# Sheet1.net
KiCad netlist of a schematic drawn in Altium Designer
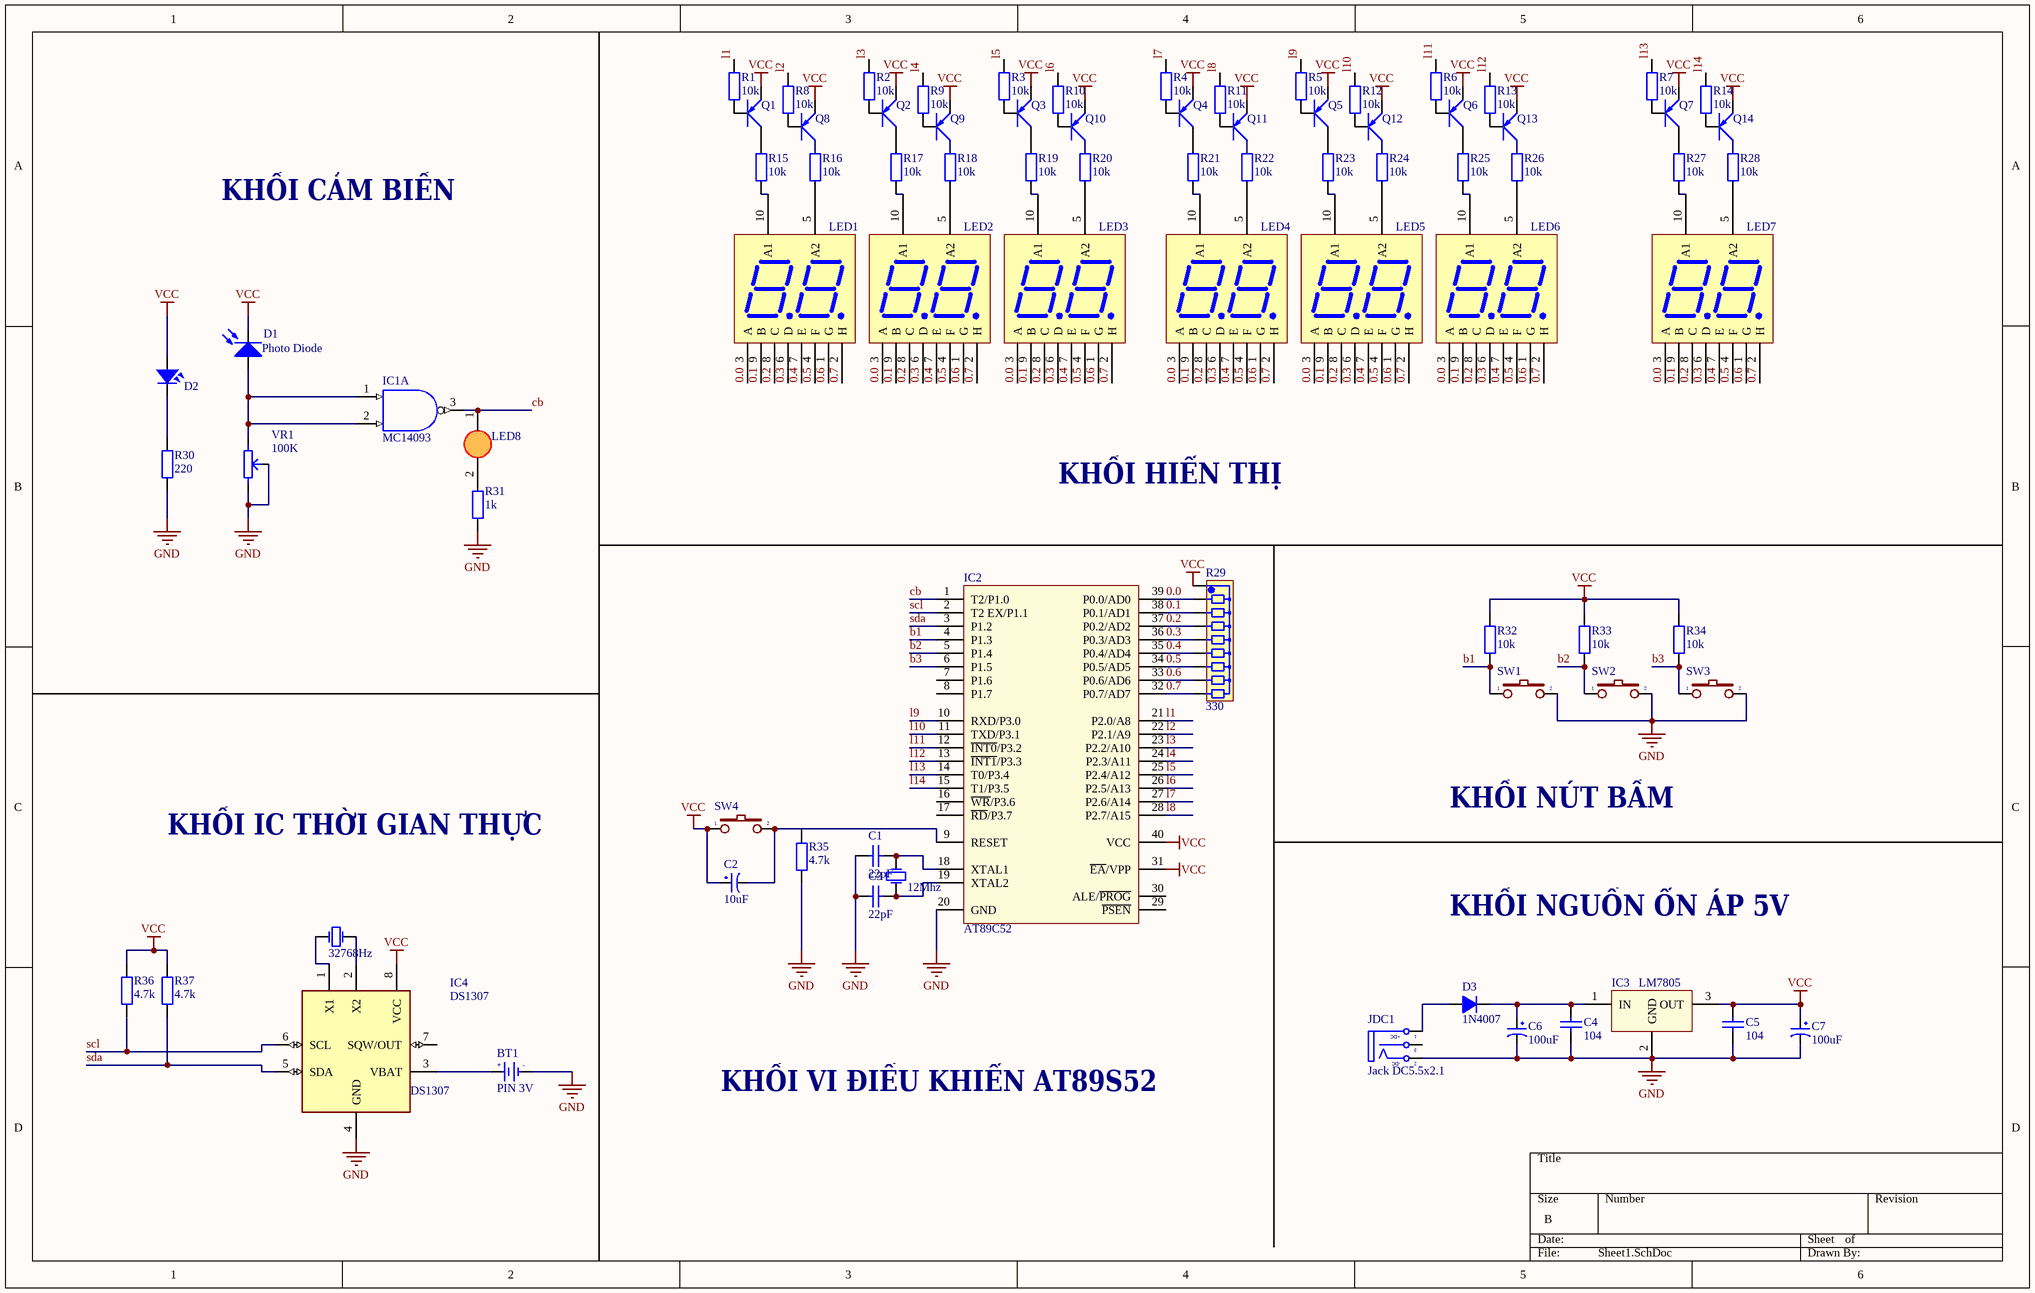
[diagram p0: Sheet1.SchDoc]

(export (version "E")
  (design (tool "Eeschema 10.0.6"))
  (components
    (comp (ref "BT1")
      (value "PIN 3V")
      (footprint "PIN3V")
      (description "Battery 3VDC")
      (libsource (lib "THU VIEN SCH") (part "PIN 3V"))
    )
    (comp (ref "C1")
      (value "22pF")
      (footprint "tu gom")
      (description "Cắm")
      (libsource (lib "THU VIEN SCH") (part "Tu gom 22pF 50V"))
    )
    (comp (ref "C2")
      (value "10uF")
      (footprint "tu hoa 4mm")
      (description "Cắm")
      (libsource (lib "THU VIEN SCH") (part "Tu Hoa 10uF 16V 4x7"))
    )
    (comp (ref "C3")
      (value "22pF")
      (footprint "tu gom")
      (description "Cắm")
      (libsource (lib "THU VIEN SCH") (part "Tu gom 22pF 50V"))
    )
    (comp (ref "C4")
      (value "104")
      (footprint "tu gom")
      (description "Cắm")
      (libsource (lib "THU VIEN SCH") (part "Tu gom 104 50V"))
    )
    (comp (ref "C5")
      (value "104")
      (footprint "tu gom")
      (description "Cắm")
      (libsource (lib "THU VIEN SCH") (part "Tu gom 104 50V"))
    )
    (comp (ref "C6")
      (value "100uF")
      (footprint "tu hoa 5mm")
      (description "Cắm")
      (libsource (lib "THU VIEN SCH") (part "Tu Hoa 100uF 16V 5x7"))
    )
    (comp (ref "C7")
      (value "100uF")
      (footprint "tu hoa 5mm")
      (description "Cắm")
      (libsource (lib "THU VIEN SCH") (part "Tu Hoa 100uF 16V 5x7"))
    )
    (comp (ref "D1")
      (value "Photo Diode")
      (footprint "LED-5-Green")
      (description "Photosensitive Diode")
      (libsource (lib "syhaunguyen") (part "Photo Diode"))
    )
    (comp (ref "D2")
      (value "Phat")
      (footprint "LED-3")
      (description "LED phat hong ngoai")
      (libsource (lib "syhaunguyen") (part "LED"))
    )
    (comp (ref "D3")
      (value "1N4007")
      (footprint "Diode 1N4007")
      (description "Diode 1A")
      (libsource (lib "syhaunguyen") (part "D1A"))
    )
    (comp (ref "IC1")
      (value "MC14093")
      (footprint "DIP14/W0.3")
      (description "Quad 2-Input NAND Schmitt Trigger")
      (libsource (lib "syhaunguyen") (part "MC14093"))
    )
    (comp (ref "IC2")
      (value "AT89C52")
      (footprint "DIP40/W0.6")
      (description "Cắm")
      (libsource (lib "THU VIEN SCH") (part "AT89C52"))
    )
    (comp (ref "IC3")
      (value "LM7805")
      (footprint "QTO-220")
      (description "On ap +, from + 5 to + 24VDC")
      (libsource (lib "THU VIEN SCH") (part "LM78xx"))
    )
    (comp (ref "IC4")
      (value "DS1307")
      (footprint "DIL08")
      (description "Real Time Clock (RTC) IC Clock/Calendar 56B IÂ²C, 2-Wire Serial 8-SOIC (0.154, 3.90mm Width)")
      (fields (field (name "MF") "Analog Devices"))
      (libsource (lib "DS1307") (part "DS1307"))
    )
    (comp (ref "JDC1")
      (value "Jack DC5.5x2.1")
      (footprint "DC-IN")
      (description "Cắm")
      (libsource (lib "THU VIEN SCH") (part "Jac_DC"))
    )
    (comp (ref "LED1")
      (value "Led 7 0.36 3 Số Anot ( Sáng Đỏ)")
      (footprint "LED 7 THANH_0.36x2")
      (description "Cắm")
      (libsource (lib "THU VIEN SCH") (part "LED 7 2 SO 0.36_A"))
    )
    (comp (ref "LED2")
      (value "Led 7 0.36 3 Số Anot ( Sáng Đỏ)")
      (footprint "LED 7 THANH_0.36x2")
      (description "Cắm")
      (libsource (lib "THU VIEN SCH") (part "LED 7 2 SO 0.36_A"))
    )
    (comp (ref "LED3")
      (value "Led 7 0.36 3 Số Anot ( Sáng Đỏ)")
      (footprint "LED 7 THANH_0.36x2")
      (description "Cắm")
      (libsource (lib "THU VIEN SCH") (part "LED 7 2 SO 0.36_A"))
    )
    (comp (ref "LED4")
      (value "Led 7 0.36 3 Số Anot ( Sáng Đỏ)")
      (footprint "LED 7 THANH_0.36x2")
      (description "Cắm")
      (libsource (lib "THU VIEN SCH") (part "LED 7 2 SO 0.36_A"))
    )
    (comp (ref "LED5")
      (value "Led 7 0.36 3 Số Anot ( Sáng Đỏ)")
      (footprint "LED 7 THANH_0.36x2")
      (description "Cắm")
      (libsource (lib "THU VIEN SCH") (part "LED 7 2 SO 0.36_A"))
    )
    (comp (ref "LED6")
      (value "Led 7 0.36 3 Số Anot ( Sáng Đỏ)")
      (footprint "LED 7 THANH_0.36x2")
      (description "Cắm")
      (libsource (lib "THU VIEN SCH") (part "LED 7 2 SO 0.36_A"))
    )
    (comp (ref "LED7")
      (value "Led 7 0.36 3 Số Anot ( Sáng Đỏ)")
      (footprint "LED 7 THANH_0.36x2")
      (description "Cắm")
      (libsource (lib "THU VIEN SCH") (part "LED 7 2 SO 0.36_A"))
    )
    (comp (ref "LED8")
      (value "~")
      (footprint "LED 3mm Do")
      (description "Cắm")
      (libsource (lib "THU VIEN SCH") (part "LED 3mm Do"))
    )
    (comp (ref "Q1")
      (value "~")
      (footprint "QTO-92")
      (description "PNP 600mW, ECB")
      (libsource (lib "syhaunguyen") (part "A1015"))
    )
    (comp (ref "Q2")
      (value "~")
      (footprint "QTO-92")
      (description "PNP 600mW, ECB")
      (libsource (lib "syhaunguyen") (part "A1015"))
    )
    (comp (ref "Q3")
      (value "~")
      (footprint "QTO-92")
      (description "PNP 600mW, ECB")
      (libsource (lib "syhaunguyen") (part "A1015"))
    )
    (comp (ref "Q4")
      (value "~")
      (footprint "QTO-92")
      (description "PNP 600mW, ECB")
      (libsource (lib "syhaunguyen") (part "A1015"))
    )
    (comp (ref "Q5")
      (value "~")
      (footprint "QTO-92")
      (description "PNP 600mW, ECB")
      (libsource (lib "syhaunguyen") (part "A1015"))
    )
    (comp (ref "Q6")
      (value "~")
      (footprint "QTO-92")
      (description "PNP 600mW, ECB")
      (libsource (lib "syhaunguyen") (part "A1015"))
    )
    (comp (ref "Q7")
      (value "~")
      (footprint "QTO-92")
      (description "PNP 600mW, ECB")
      (libsource (lib "syhaunguyen") (part "A1015"))
    )
    (comp (ref "Q8")
      (value "~")
      (footprint "QTO-92")
      (description "PNP 600mW, ECB")
      (libsource (lib "syhaunguyen") (part "A1015"))
    )
    (comp (ref "Q9")
      (value "~")
      (footprint "QTO-92")
      (description "PNP 600mW, ECB")
      (libsource (lib "syhaunguyen") (part "A1015"))
    )
    (comp (ref "Q10")
      (value "~")
      (footprint "QTO-92")
      (description "PNP 600mW, ECB")
      (libsource (lib "syhaunguyen") (part "A1015"))
    )
    (comp (ref "Q11")
      (value "~")
      (footprint "QTO-92")
      (description "PNP 600mW, ECB")
      (libsource (lib "syhaunguyen") (part "A1015"))
    )
    (comp (ref "Q12")
      (value "~")
      (footprint "QTO-92")
      (description "PNP 600mW, ECB")
      (libsource (lib "syhaunguyen") (part "A1015"))
    )
    (comp (ref "Q13")
      (value "~")
      (footprint "QTO-92")
      (description "PNP 600mW, ECB")
      (libsource (lib "syhaunguyen") (part "A1015"))
    )
    (comp (ref "Q14")
      (value "~")
      (footprint "QTO-92")
      (description "PNP 600mW, ECB")
      (libsource (lib "syhaunguyen") (part "A1015"))
    )
    (comp (ref "R1")
      (value "10k")
      (footprint "tro vach 1/4w")
      (description "Cắm")
      (libsource (lib "THU VIEN SCH") (part "Tro Vach 1/4W 1% 10k"))
    )
    (comp (ref "R2")
      (value "10k")
      (footprint "tro vach 1/4w")
      (description "Cắm")
      (libsource (lib "THU VIEN SCH") (part "Tro Vach 1/4W 1% 10k"))
    )
    (comp (ref "R3")
      (value "10k")
      (footprint "tro vach 1/4w")
      (description "Cắm")
      (libsource (lib "THU VIEN SCH") (part "Tro Vach 1/4W 1% 10k"))
    )
    (comp (ref "R4")
      (value "10k")
      (footprint "tro vach 1/4w")
      (description "Cắm")
      (libsource (lib "THU VIEN SCH") (part "Tro Vach 1/4W 1% 10k"))
    )
    (comp (ref "R5")
      (value "10k")
      (footprint "tro vach 1/4w")
      (description "Cắm")
      (libsource (lib "THU VIEN SCH") (part "Tro Vach 1/4W 1% 10k"))
    )
    (comp (ref "R6")
      (value "10k")
      (footprint "tro vach 1/4w")
      (description "Cắm")
      (libsource (lib "THU VIEN SCH") (part "Tro Vach 1/4W 1% 10k"))
    )
    (comp (ref "R7")
      (value "10k")
      (footprint "tro vach 1/4w")
      (description "Cắm")
      (libsource (lib "THU VIEN SCH") (part "Tro Vach 1/4W 1% 10k"))
    )
    (comp (ref "R8")
      (value "10k")
      (footprint "tro vach 1/4w")
      (description "Cắm")
      (libsource (lib "THU VIEN SCH") (part "Tro Vach 1/4W 1% 10k"))
    )
    (comp (ref "R9")
      (value "10k")
      (footprint "tro vach 1/4w")
      (description "Cắm")
      (libsource (lib "THU VIEN SCH") (part "Tro Vach 1/4W 1% 10k"))
    )
    (comp (ref "R10")
      (value "10k")
      (footprint "tro vach 1/4w")
      (description "Cắm")
      (libsource (lib "THU VIEN SCH") (part "Tro Vach 1/4W 1% 10k"))
    )
    (comp (ref "R11")
      (value "10k")
      (footprint "tro vach 1/4w")
      (description "Cắm")
      (libsource (lib "THU VIEN SCH") (part "Tro Vach 1/4W 1% 10k"))
    )
    (comp (ref "R12")
      (value "10k")
      (footprint "tro vach 1/4w")
      (description "Cắm")
      (libsource (lib "THU VIEN SCH") (part "Tro Vach 1/4W 1% 10k"))
    )
    (comp (ref "R13")
      (value "10k")
      (footprint "tro vach 1/4w")
      (description "Cắm")
      (libsource (lib "THU VIEN SCH") (part "Tro Vach 1/4W 1% 10k"))
    )
    (comp (ref "R14")
      (value "10k")
      (footprint "tro vach 1/4w")
      (description "Cắm")
      (libsource (lib "THU VIEN SCH") (part "Tro Vach 1/4W 1% 10k"))
    )
    (comp (ref "R15")
      (value "10k")
      (footprint "tro vach 1/4w")
      (description "Cắm")
      (libsource (lib "THU VIEN SCH") (part "Tro Vach 1/4W 1% 10k"))
    )
    (comp (ref "R16")
      (value "10k")
      (footprint "tro vach 1/4w")
      (description "Cắm")
      (libsource (lib "THU VIEN SCH") (part "Tro Vach 1/4W 1% 10k"))
    )
    (comp (ref "R17")
      (value "10k")
      (footprint "tro vach 1/4w")
      (description "Cắm")
      (libsource (lib "THU VIEN SCH") (part "Tro Vach 1/4W 1% 10k"))
    )
    (comp (ref "R18")
      (value "10k")
      (footprint "tro vach 1/4w")
      (description "Cắm")
      (libsource (lib "THU VIEN SCH") (part "Tro Vach 1/4W 1% 10k"))
    )
    (comp (ref "R19")
      (value "10k")
      (footprint "tro vach 1/4w")
      (description "Cắm")
      (libsource (lib "THU VIEN SCH") (part "Tro Vach 1/4W 1% 10k"))
    )
    (comp (ref "R20")
      (value "10k")
      (footprint "tro vach 1/4w")
      (description "Cắm")
      (libsource (lib "THU VIEN SCH") (part "Tro Vach 1/4W 1% 10k"))
    )
    (comp (ref "R21")
      (value "10k")
      (footprint "tro vach 1/4w")
      (description "Cắm")
      (libsource (lib "THU VIEN SCH") (part "Tro Vach 1/4W 1% 10k"))
    )
    (comp (ref "R22")
      (value "10k")
      (footprint "tro vach 1/4w")
      (description "Cắm")
      (libsource (lib "THU VIEN SCH") (part "Tro Vach 1/4W 1% 10k"))
    )
    (comp (ref "R23")
      (value "10k")
      (footprint "tro vach 1/4w")
      (description "Cắm")
      (libsource (lib "THU VIEN SCH") (part "Tro Vach 1/4W 1% 10k"))
    )
    (comp (ref "R24")
      (value "10k")
      (footprint "tro vach 1/4w")
      (description "Cắm")
      (libsource (lib "THU VIEN SCH") (part "Tro Vach 1/4W 1% 10k"))
    )
    (comp (ref "R25")
      (value "10k")
      (footprint "tro vach 1/4w")
      (description "Cắm")
      (libsource (lib "THU VIEN SCH") (part "Tro Vach 1/4W 1% 10k"))
    )
    (comp (ref "R26")
      (value "10k")
      (footprint "tro vach 1/4w")
      (description "Cắm")
      (libsource (lib "THU VIEN SCH") (part "Tro Vach 1/4W 1% 10k"))
    )
    (comp (ref "R27")
      (value "10k")
      (footprint "tro vach 1/4w")
      (description "Cắm")
      (libsource (lib "THU VIEN SCH") (part "Tro Vach 1/4W 1% 10k"))
    )
    (comp (ref "R28")
      (value "10k")
      (footprint "tro vach 1/4w")
      (description "Cắm")
      (libsource (lib "THU VIEN SCH") (part "Tro Vach 1/4W 1% 10k"))
    )
    (comp (ref "R29")
      (value "330")
      (footprint "tro bang a9")
      (description "Cắm")
      (libsource (lib "THU VIEN SCH") (part "Tro Bang A9 330R"))
    )
    (comp (ref "R30")
      (value "220")
      (footprint "tro vach 1/4w")
      (description "Cắm")
      (libsource (lib "THU VIEN SCH") (part "Tro Vach 1/4W 1% 10k"))
    )
    (comp (ref "R31")
      (value "1k")
      (footprint "tro vach 1/4w")
      (description "Cắm")
      (libsource (lib "THU VIEN SCH") (part "Tro Vach 1/4W 5% 1k"))
    )
    (comp (ref "R32")
      (value "10k")
      (footprint "tro vach 1/4w")
      (description "Cắm")
      (libsource (lib "THU VIEN SCH") (part "Tro Vach 1/4W 1% 10k"))
    )
    (comp (ref "R33")
      (value "10k")
      (footprint "tro vach 1/4w")
      (description "Cắm")
      (libsource (lib "THU VIEN SCH") (part "Tro Vach 1/4W 1% 10k"))
    )
    (comp (ref "R34")
      (value "10k")
      (footprint "tro vach 1/4w")
      (description "Cắm")
      (libsource (lib "THU VIEN SCH") (part "Tro Vach 1/4W 1% 10k"))
    )
    (comp (ref "R35")
      (value "4.7k")
      (footprint "tro vach 1/4w")
      (description "Cắm")
      (libsource (lib "THU VIEN SCH") (part "Tro Vach 1/4W 1% 4.7k"))
    )
    (comp (ref "R36")
      (value "4.7k")
      (footprint "tro vach 1/4w")
      (description "Cắm")
      (libsource (lib "THU VIEN SCH") (part "Tro Vach 1/4W 1% 4.7k"))
    )
    (comp (ref "R37")
      (value "4.7k")
      (footprint "tro vach 1/4w")
      (description "Cắm")
      (libsource (lib "THU VIEN SCH") (part "Tro Vach 1/4W 1% 4.7k"))
    )
    (comp (ref "SW1")
      (value "~")
      (footprint "SW2")
      (description "Cắm")
      (libsource (lib "THU VIEN SCH") (part "Nut Nhan 2 Chan ( Dip )"))
    )
    (comp (ref "SW2")
      (value "~")
      (footprint "SW2")
      (description "Cắm")
      (libsource (lib "THU VIEN SCH") (part "Nut Nhan 2 Chan ( Dip )"))
    )
    (comp (ref "SW3")
      (value "~")
      (footprint "SW2")
      (description "Cắm")
      (libsource (lib "THU VIEN SCH") (part "Nut Nhan 2 Chan ( Dip )"))
    )
    (comp (ref "SW4")
      (value "~")
      (footprint "SW2")
      (description "Cắm")
      (libsource (lib "THU VIEN SCH") (part "Nut Nhan 2 Chan ( Dip )"))
    )
    (comp (ref "VR1")
      (value "100K")
      (footprint "BIEN TRO TAM GIAC")
      (description "Cắm")
      (libsource (lib "THU VIEN SCH") (part "Bien tro tam giac 1K"))
    )
    (comp (ref "Y1")
      (value "12Mhz")
      (footprint "THACH ANH CAM")
      (description "Cắm")
      (libsource (lib "THU VIEN SCH") (part "Thach Anh 8Mhz DIP"))
    )
    (comp (ref "Y2")
      (value "32768Hz")
      (footprint "XT2")
      (description "Cắm")
      (libsource (lib "THU VIEN SCH") (part "Thach Anh 8Mhz DIP"))
    )
  )
  (nets
    (net (code "1") (name "/0.0") (class "Default")
      (node (ref "IC2") (pin "39") (pinfunction "P0.0/AD0_39") (pintype "passive"))
      (node (ref "LED1") (pin "3") (pinfunction "A_3") (pintype "passive"))
      (node (ref "LED2") (pin "3") (pinfunction "A_3") (pintype "passive"))
      (node (ref "LED3") (pin "3") (pinfunction "A_3") (pintype "passive"))
      (node (ref "LED4") (pin "3") (pinfunction "A_3") (pintype "passive"))
      (node (ref "LED5") (pin "3") (pinfunction "A_3") (pintype "passive"))
      (node (ref "LED6") (pin "3") (pinfunction "A_3") (pintype "passive"))
      (node (ref "LED7") (pin "3") (pinfunction "A_3") (pintype "passive"))
      (node (ref "R29") (pin "2") (pinfunction "2_2") (pintype "passive"))
    )
    (net (code "2") (name "/0.1") (class "Default")
      (node (ref "IC2") (pin "38") (pinfunction "P0.1/AD1_38") (pintype "passive"))
      (node (ref "LED1") (pin "9") (pinfunction "B_9") (pintype "passive"))
      (node (ref "LED2") (pin "9") (pinfunction "B_9") (pintype "passive"))
      (node (ref "LED3") (pin "9") (pinfunction "B_9") (pintype "passive"))
      (node (ref "LED4") (pin "9") (pinfunction "B_9") (pintype "passive"))
      (node (ref "LED5") (pin "9") (pinfunction "B_9") (pintype "passive"))
      (node (ref "LED6") (pin "9") (pinfunction "B_9") (pintype "passive"))
      (node (ref "LED7") (pin "9") (pinfunction "B_9") (pintype "passive"))
      (node (ref "R29") (pin "3") (pinfunction "3_3") (pintype "passive"))
    )
    (net (code "3") (name "/0.2") (class "Default")
      (node (ref "IC2") (pin "37") (pinfunction "P0.2/AD2_37") (pintype "passive"))
      (node (ref "LED1") (pin "8") (pinfunction "C_8") (pintype "passive"))
      (node (ref "LED2") (pin "8") (pinfunction "C_8") (pintype "passive"))
      (node (ref "LED3") (pin "8") (pinfunction "C_8") (pintype "passive"))
      (node (ref "LED4") (pin "8") (pinfunction "C_8") (pintype "passive"))
      (node (ref "LED5") (pin "8") (pinfunction "C_8") (pintype "passive"))
      (node (ref "LED6") (pin "8") (pinfunction "C_8") (pintype "passive"))
      (node (ref "LED7") (pin "8") (pinfunction "C_8") (pintype "passive"))
      (node (ref "R29") (pin "4") (pinfunction "4_4") (pintype "passive"))
    )
    (net (code "4") (name "/0.3") (class "Default")
      (node (ref "IC2") (pin "36") (pinfunction "P0.3/AD3_36") (pintype "passive"))
      (node (ref "LED1") (pin "6") (pinfunction "D_6") (pintype "passive"))
      (node (ref "LED2") (pin "6") (pinfunction "D_6") (pintype "passive"))
      (node (ref "LED3") (pin "6") (pinfunction "D_6") (pintype "passive"))
      (node (ref "LED4") (pin "6") (pinfunction "D_6") (pintype "passive"))
      (node (ref "LED5") (pin "6") (pinfunction "D_6") (pintype "passive"))
      (node (ref "LED6") (pin "6") (pinfunction "D_6") (pintype "passive"))
      (node (ref "LED7") (pin "6") (pinfunction "D_6") (pintype "passive"))
      (node (ref "R29") (pin "5") (pinfunction "5_5") (pintype "passive"))
    )
    (net (code "5") (name "/0.4") (class "Default")
      (node (ref "IC2") (pin "35") (pinfunction "P0.4/AD4_35") (pintype "passive"))
      (node (ref "LED1") (pin "7") (pinfunction "E_7") (pintype "passive"))
      (node (ref "LED2") (pin "7") (pinfunction "E_7") (pintype "passive"))
      (node (ref "LED3") (pin "7") (pinfunction "E_7") (pintype "passive"))
      (node (ref "LED4") (pin "7") (pinfunction "E_7") (pintype "passive"))
      (node (ref "LED5") (pin "7") (pinfunction "E_7") (pintype "passive"))
      (node (ref "LED6") (pin "7") (pinfunction "E_7") (pintype "passive"))
      (node (ref "LED7") (pin "7") (pinfunction "E_7") (pintype "passive"))
      (node (ref "R29") (pin "6") (pinfunction "6_6") (pintype "passive"))
    )
    (net (code "6") (name "/0.5") (class "Default")
      (node (ref "IC2") (pin "34") (pinfunction "P0.5/AD5_34") (pintype "passive"))
      (node (ref "LED1") (pin "4") (pinfunction "F_4") (pintype "passive"))
      (node (ref "LED2") (pin "4") (pinfunction "F_4") (pintype "passive"))
      (node (ref "LED3") (pin "4") (pinfunction "F_4") (pintype "passive"))
      (node (ref "LED4") (pin "4") (pinfunction "F_4") (pintype "passive"))
      (node (ref "LED5") (pin "4") (pinfunction "F_4") (pintype "passive"))
      (node (ref "LED6") (pin "4") (pinfunction "F_4") (pintype "passive"))
      (node (ref "LED7") (pin "4") (pinfunction "F_4") (pintype "passive"))
      (node (ref "R29") (pin "7") (pinfunction "7_7") (pintype "passive"))
    )
    (net (code "7") (name "/0.6") (class "Default")
      (node (ref "IC2") (pin "33") (pinfunction "P0.6/AD6_33") (pintype "passive"))
      (node (ref "LED1") (pin "1") (pinfunction "G_1") (pintype "passive"))
      (node (ref "LED2") (pin "1") (pinfunction "G_1") (pintype "passive"))
      (node (ref "LED3") (pin "1") (pinfunction "G_1") (pintype "passive"))
      (node (ref "LED4") (pin "1") (pinfunction "G_1") (pintype "passive"))
      (node (ref "LED5") (pin "1") (pinfunction "G_1") (pintype "passive"))
      (node (ref "LED6") (pin "1") (pinfunction "G_1") (pintype "passive"))
      (node (ref "LED7") (pin "1") (pinfunction "G_1") (pintype "passive"))
      (node (ref "R29") (pin "8") (pinfunction "8_8") (pintype "passive"))
    )
    (net (code "8") (name "/0.7") (class "Default")
      (node (ref "IC2") (pin "32") (pinfunction "P0.7/AD7_32") (pintype "passive"))
      (node (ref "LED1") (pin "2") (pinfunction "H_2") (pintype "passive"))
      (node (ref "LED2") (pin "2") (pinfunction "H_2") (pintype "passive"))
      (node (ref "LED3") (pin "2") (pinfunction "H_2") (pintype "passive"))
      (node (ref "LED4") (pin "2") (pinfunction "H_2") (pintype "passive"))
      (node (ref "LED5") (pin "2") (pinfunction "H_2") (pintype "passive"))
      (node (ref "LED6") (pin "2") (pinfunction "H_2") (pintype "passive"))
      (node (ref "LED7") (pin "2") (pinfunction "H_2") (pintype "passive"))
      (node (ref "R29") (pin "9") (pinfunction "9_9") (pintype "passive"))
    )
    (net (code "9") (name "/b1") (class "Default")
      (node (ref "IC2") (pin "4") (pinfunction "P1.3_4") (pintype "passive"))
      (node (ref "R32") (pin "1") (pinfunction "1_1") (pintype "passive"))
      (node (ref "SW1") (pin "1") (pinfunction "1_1") (pintype "passive"))
    )
    (net (code "10") (name "/b2") (class "Default")
      (node (ref "IC2") (pin "5") (pinfunction "P1.4_5") (pintype "passive"))
      (node (ref "R33") (pin "1") (pinfunction "1_1") (pintype "passive"))
      (node (ref "SW2") (pin "1") (pinfunction "1_1") (pintype "passive"))
    )
    (net (code "11") (name "/b3") (class "Default")
      (node (ref "IC2") (pin "6") (pinfunction "P1.5_6") (pintype "passive"))
      (node (ref "R34") (pin "1") (pinfunction "1_1") (pintype "passive"))
      (node (ref "SW3") (pin "1") (pinfunction "1_1") (pintype "passive"))
    )
    (net (code "12") (name "/cb") (class "Default")
      (node (ref "IC1") (pin "3") (pinfunction "~{Y}_3") (pintype "output"))
      (node (ref "IC2") (pin "1") (pinfunction "T2/P1.0_1") (pintype "passive"))
      (node (ref "LED8") (pin "1") (pinfunction "A_1") (pintype "passive"))
    )
    (net (code "13") (name "/l1") (class "Default")
      (node (ref "IC2") (pin "21") (pinfunction "P2.0/A8_21") (pintype "passive"))
      (node (ref "R1") (pin "2") (pinfunction "2_2") (pintype "passive"))
    )
    (net (code "14") (name "/l2") (class "Default")
      (node (ref "IC2") (pin "22") (pinfunction "P2.1/A9_22") (pintype "passive"))
      (node (ref "R8") (pin "2") (pinfunction "2_2") (pintype "passive"))
    )
    (net (code "15") (name "/l3") (class "Default")
      (node (ref "IC2") (pin "23") (pinfunction "P2.2/A10_23") (pintype "passive"))
      (node (ref "R2") (pin "2") (pinfunction "2_2") (pintype "passive"))
    )
    (net (code "16") (name "/l4") (class "Default")
      (node (ref "IC2") (pin "24") (pinfunction "P2.3/A11_24") (pintype "passive"))
      (node (ref "R9") (pin "2") (pinfunction "2_2") (pintype "passive"))
    )
    (net (code "17") (name "/l5") (class "Default")
      (node (ref "IC2") (pin "25") (pinfunction "P2.4/A12_25") (pintype "passive"))
      (node (ref "R3") (pin "2") (pinfunction "2_2") (pintype "passive"))
    )
    (net (code "18") (name "/l6") (class "Default")
      (node (ref "IC2") (pin "26") (pinfunction "P2.5/A13_26") (pintype "passive"))
      (node (ref "R10") (pin "2") (pinfunction "2_2") (pintype "passive"))
    )
    (net (code "19") (name "/l7") (class "Default")
      (node (ref "IC2") (pin "27") (pinfunction "P2.6/A14_27") (pintype "passive"))
      (node (ref "R4") (pin "2") (pinfunction "2_2") (pintype "passive"))
    )
    (net (code "20") (name "/l8") (class "Default")
      (node (ref "IC2") (pin "28") (pinfunction "P2.7/A15_28") (pintype "passive"))
      (node (ref "R11") (pin "2") (pinfunction "2_2") (pintype "passive"))
    )
    (net (code "21") (name "/l9") (class "Default")
      (node (ref "IC2") (pin "10") (pinfunction "RXD/P3.0_10") (pintype "passive"))
      (node (ref "R5") (pin "2") (pinfunction "2_2") (pintype "passive"))
    )
    (net (code "22") (name "/l10") (class "Default")
      (node (ref "IC2") (pin "11") (pinfunction "TXD/P3.1_11") (pintype "passive"))
      (node (ref "R12") (pin "2") (pinfunction "2_2") (pintype "passive"))
    )
    (net (code "23") (name "/l11") (class "Default")
      (node (ref "IC2") (pin "12") (pinfunction "~{INT0}/P3.2_12") (pintype "passive"))
      (node (ref "R6") (pin "2") (pinfunction "2_2") (pintype "passive"))
    )
    (net (code "24") (name "/l12") (class "Default")
      (node (ref "IC2") (pin "13") (pinfunction "~{INT1}/P3.3_13") (pintype "passive"))
      (node (ref "R13") (pin "2") (pinfunction "2_2") (pintype "passive"))
    )
    (net (code "25") (name "/l13") (class "Default")
      (node (ref "IC2") (pin "14") (pinfunction "T0/P3.4_14") (pintype "passive"))
      (node (ref "R7") (pin "2") (pinfunction "2_2") (pintype "passive"))
    )
    (net (code "26") (name "/l14") (class "Default")
      (node (ref "IC2") (pin "15") (pinfunction "T1/P3.5_15") (pintype "passive"))
      (node (ref "R14") (pin "2") (pinfunction "2_2") (pintype "passive"))
    )
    (net (code "27") (name "/scl") (class "Default")
      (node (ref "IC2") (pin "2") (pinfunction "T2_EX/P1.1_2") (pintype "passive"))
      (node (ref "IC4") (pin "6") (pinfunction "SCL_6") (pintype "bidirectional"))
      (node (ref "R36") (pin "1") (pinfunction "1_1") (pintype "passive"))
    )
    (net (code "28") (name "/sda") (class "Default")
      (node (ref "IC2") (pin "3") (pinfunction "P1.2_3") (pintype "passive"))
      (node (ref "IC4") (pin "5") (pinfunction "SDA_5") (pintype "bidirectional"))
      (node (ref "R37") (pin "1") (pinfunction "1_1") (pintype "passive"))
    )
    (net (code "29") (name "GND") (class "Default")
      (node (ref "BT1") (pin "2") (pinfunction "GND_2") (pintype "passive"))
      (node (ref "C1") (pin "2") (pinfunction "2_2") (pintype "passive"))
      (node (ref "C3") (pin "2") (pinfunction "2_2") (pintype "passive"))
      (node (ref "C4") (pin "2") (pinfunction "2_2") (pintype "passive"))
      (node (ref "C5") (pin "2") (pinfunction "2_2") (pintype "passive"))
      (node (ref "C6") (pin "2") (pinfunction "2_2") (pintype "passive"))
      (node (ref "C7") (pin "2") (pinfunction "2_2") (pintype "passive"))
      (node (ref "IC1") (pin "7") (pinfunction "GND_7") (pintype "power_in"))
      (node (ref "IC2") (pin "20") (pinfunction "GND_20") (pintype "open_emitter"))
      (node (ref "IC3") (pin "2") (pinfunction "GND_2") (pintype "passive"))
      (node (ref "IC4") (pin "4") (pinfunction "GND_4") (pintype "power_in"))
      (node (ref "JDC1") (pin "2") (pinfunction "TN_2") (pintype "passive"))
      (node (ref "R30") (pin "1") (pinfunction "1_1") (pintype "passive"))
      (node (ref "R31") (pin "1") (pinfunction "1_1") (pintype "passive"))
      (node (ref "R35") (pin "1") (pinfunction "1_1") (pintype "passive"))
      (node (ref "SW1") (pin "2") (pinfunction "2_2") (pintype "passive"))
      (node (ref "SW2") (pin "2") (pinfunction "2_2") (pintype "passive"))
      (node (ref "SW3") (pin "2") (pinfunction "2_2") (pintype "passive"))
      (node (ref "VR1") (pin "2") (pinfunction "2_2") (pintype "passive"))
      (node (ref "VR1") (pin "3") (pinfunction "3_3") (pintype "passive"))
    )
    (net (code "30") (name "Net-(BT1-+3V)") (class "Default")
      (node (ref "BT1") (pin "1") (pinfunction "+3V_1") (pintype "passive"))
      (node (ref "IC4") (pin "3") (pinfunction "VBAT_3") (pintype "power_in"))
    )
    (net (code "31") (name "Net-(D1-A)") (class "Default")
      (node (ref "D1") (pin "1") (pinfunction "A_1") (pintype "passive"))
      (node (ref "IC1") (pin "1") (pinfunction "A_1") (pintype "input"))
      (node (ref "IC1") (pin "2") (pinfunction "B_2") (pintype "input"))
      (node (ref "VR1") (pin "1") (pinfunction "1_1") (pintype "passive"))
    )
    (net (code "32") (name "Net-(D2-Pad2)") (class "Default")
      (node (ref "D2") (pin "2") (pinfunction "2_2") (pintype "passive"))
      (node (ref "R30") (pin "2") (pinfunction "2_2") (pintype "passive"))
    )
    (net (code "33") (name "Net-(D3-A)") (class "Default")
      (node (ref "D3") (pin "1") (pinfunction "A_1") (pintype "passive"))
      (node (ref "JDC1") (pin "1") (pinfunction "T_1") (pintype "passive"))
    )
    (net (code "34") (name "Net-(D3-K)") (class "Default")
      (node (ref "C4") (pin "1") (pinfunction "1_1") (pintype "passive"))
      (node (ref "C6") (pin "1") (pinfunction "1_1") (pintype "passive"))
      (node (ref "D3") (pin "2") (pinfunction "K_2") (pintype "passive"))
      (node (ref "IC3") (pin "1") (pinfunction "IN_1") (pintype "passive"))
    )
    (net (code "35") (name "Net-(IC2-RESET)") (class "Default")
      (node (ref "C2") (pin "2") (pinfunction "2_2") (pintype "passive"))
      (node (ref "IC2") (pin "9") (pinfunction "RESET_9") (pintype "passive"))
      (node (ref "SW4") (pin "2") (pinfunction "2_2") (pintype "passive"))
    )
    (net (code "36") (name "Net-(IC2-XTAL1)") (class "Default")
      (node (ref "C1") (pin "1") (pinfunction "1_1") (pintype "passive"))
      (node (ref "IC2") (pin "18") (pinfunction "XTAL1_18") (pintype "passive"))
      (node (ref "Y1") (pin "2") (pinfunction "OSC2_2") (pintype "passive"))
    )
    (net (code "37") (name "Net-(IC2-XTAL2)") (class "Default")
      (node (ref "C3") (pin "1") (pinfunction "1_1") (pintype "passive"))
      (node (ref "IC2") (pin "19") (pinfunction "XTAL2_19") (pintype "passive"))
      (node (ref "Y1") (pin "1") (pinfunction "OSC1_1") (pintype "passive"))
    )
    (net (code "38") (name "Net-(IC4-X1)") (class "Default")
      (node (ref "IC4") (pin "1") (pinfunction "X1_1") (pintype "passive"))
      (node (ref "Y2") (pin "1") (pinfunction "OSC1_1") (pintype "passive"))
    )
    (net (code "39") (name "Net-(IC4-X2)") (class "Default")
      (node (ref "IC4") (pin "2") (pinfunction "X2_2") (pintype "passive"))
      (node (ref "Y2") (pin "2") (pinfunction "OSC2_2") (pintype "passive"))
    )
    (net (code "40") (name "Net-(LED1-A1)") (class "Default")
      (node (ref "LED1") (pin "10") (pinfunction "A1_10") (pintype "passive"))
      (node (ref "R15") (pin "1") (pinfunction "1_1") (pintype "passive"))
    )
    (net (code "41") (name "Net-(LED1-A2)") (class "Default")
      (node (ref "LED1") (pin "5") (pinfunction "A2_5") (pintype "passive"))
      (node (ref "R16") (pin "1") (pinfunction "1_1") (pintype "passive"))
    )
    (net (code "42") (name "Net-(LED2-A1)") (class "Default")
      (node (ref "LED2") (pin "10") (pinfunction "A1_10") (pintype "passive"))
      (node (ref "R17") (pin "1") (pinfunction "1_1") (pintype "passive"))
    )
    (net (code "43") (name "Net-(LED2-A2)") (class "Default")
      (node (ref "LED2") (pin "5") (pinfunction "A2_5") (pintype "passive"))
      (node (ref "R18") (pin "1") (pinfunction "1_1") (pintype "passive"))
    )
    (net (code "44") (name "Net-(LED3-A1)") (class "Default")
      (node (ref "LED3") (pin "10") (pinfunction "A1_10") (pintype "passive"))
      (node (ref "R19") (pin "1") (pinfunction "1_1") (pintype "passive"))
    )
    (net (code "45") (name "Net-(LED3-A2)") (class "Default")
      (node (ref "LED3") (pin "5") (pinfunction "A2_5") (pintype "passive"))
      (node (ref "R20") (pin "1") (pinfunction "1_1") (pintype "passive"))
    )
    (net (code "46") (name "Net-(LED4-A1)") (class "Default")
      (node (ref "LED4") (pin "10") (pinfunction "A1_10") (pintype "passive"))
      (node (ref "R21") (pin "1") (pinfunction "1_1") (pintype "passive"))
    )
    (net (code "47") (name "Net-(LED4-A2)") (class "Default")
      (node (ref "LED4") (pin "5") (pinfunction "A2_5") (pintype "passive"))
      (node (ref "R22") (pin "1") (pinfunction "1_1") (pintype "passive"))
    )
    (net (code "48") (name "Net-(LED5-A1)") (class "Default")
      (node (ref "LED5") (pin "10") (pinfunction "A1_10") (pintype "passive"))
      (node (ref "R23") (pin "1") (pinfunction "1_1") (pintype "passive"))
    )
    (net (code "49") (name "Net-(LED5-A2)") (class "Default")
      (node (ref "LED5") (pin "5") (pinfunction "A2_5") (pintype "passive"))
      (node (ref "R24") (pin "1") (pinfunction "1_1") (pintype "passive"))
    )
    (net (code "50") (name "Net-(LED6-A1)") (class "Default")
      (node (ref "LED6") (pin "10") (pinfunction "A1_10") (pintype "passive"))
      (node (ref "R25") (pin "1") (pinfunction "1_1") (pintype "passive"))
    )
    (net (code "51") (name "Net-(LED6-A2)") (class "Default")
      (node (ref "LED6") (pin "5") (pinfunction "A2_5") (pintype "passive"))
      (node (ref "R26") (pin "1") (pinfunction "1_1") (pintype "passive"))
    )
    (net (code "52") (name "Net-(LED7-A1)") (class "Default")
      (node (ref "LED7") (pin "10") (pinfunction "A1_10") (pintype "passive"))
      (node (ref "R27") (pin "1") (pinfunction "1_1") (pintype "passive"))
    )
    (net (code "53") (name "Net-(LED7-A2)") (class "Default")
      (node (ref "LED7") (pin "5") (pinfunction "A2_5") (pintype "passive"))
      (node (ref "R28") (pin "1") (pinfunction "1_1") (pintype "passive"))
    )
    (net (code "54") (name "Net-(LED8-K)") (class "Default")
      (node (ref "LED8") (pin "2") (pinfunction "K_2") (pintype "passive"))
      (node (ref "R31") (pin "2") (pinfunction "2_2") (pintype "passive"))
    )
    (net (code "55") (name "Net-(Q1-B)") (class "Default")
      (node (ref "Q1") (pin "3") (pinfunction "B_3") (pintype "passive"))
      (node (ref "R1") (pin "1") (pinfunction "1_1") (pintype "passive"))
    )
    (net (code "56") (name "Net-(Q1-C)") (class "Default")
      (node (ref "Q1") (pin "2") (pinfunction "C_2") (pintype "passive"))
      (node (ref "R15") (pin "2") (pinfunction "2_2") (pintype "passive"))
    )
    (net (code "57") (name "Net-(Q2-B)") (class "Default")
      (node (ref "Q2") (pin "3") (pinfunction "B_3") (pintype "passive"))
      (node (ref "R2") (pin "1") (pinfunction "1_1") (pintype "passive"))
    )
    (net (code "58") (name "Net-(Q2-C)") (class "Default")
      (node (ref "Q2") (pin "2") (pinfunction "C_2") (pintype "passive"))
      (node (ref "R17") (pin "2") (pinfunction "2_2") (pintype "passive"))
    )
    (net (code "59") (name "Net-(Q3-B)") (class "Default")
      (node (ref "Q3") (pin "3") (pinfunction "B_3") (pintype "passive"))
      (node (ref "R3") (pin "1") (pinfunction "1_1") (pintype "passive"))
    )
    (net (code "60") (name "Net-(Q3-C)") (class "Default")
      (node (ref "Q3") (pin "2") (pinfunction "C_2") (pintype "passive"))
      (node (ref "R19") (pin "2") (pinfunction "2_2") (pintype "passive"))
    )
    (net (code "61") (name "Net-(Q4-B)") (class "Default")
      (node (ref "Q4") (pin "3") (pinfunction "B_3") (pintype "passive"))
      (node (ref "R4") (pin "1") (pinfunction "1_1") (pintype "passive"))
    )
    (net (code "62") (name "Net-(Q4-C)") (class "Default")
      (node (ref "Q4") (pin "2") (pinfunction "C_2") (pintype "passive"))
      (node (ref "R21") (pin "2") (pinfunction "2_2") (pintype "passive"))
    )
    (net (code "63") (name "Net-(Q5-B)") (class "Default")
      (node (ref "Q5") (pin "3") (pinfunction "B_3") (pintype "passive"))
      (node (ref "R5") (pin "1") (pinfunction "1_1") (pintype "passive"))
    )
    (net (code "64") (name "Net-(Q5-C)") (class "Default")
      (node (ref "Q5") (pin "2") (pinfunction "C_2") (pintype "passive"))
      (node (ref "R23") (pin "2") (pinfunction "2_2") (pintype "passive"))
    )
    (net (code "65") (name "Net-(Q6-B)") (class "Default")
      (node (ref "Q6") (pin "3") (pinfunction "B_3") (pintype "passive"))
      (node (ref "R6") (pin "1") (pinfunction "1_1") (pintype "passive"))
    )
    (net (code "66") (name "Net-(Q6-C)") (class "Default")
      (node (ref "Q6") (pin "2") (pinfunction "C_2") (pintype "passive"))
      (node (ref "R25") (pin "2") (pinfunction "2_2") (pintype "passive"))
    )
    (net (code "67") (name "Net-(Q7-B)") (class "Default")
      (node (ref "Q7") (pin "3") (pinfunction "B_3") (pintype "passive"))
      (node (ref "R7") (pin "1") (pinfunction "1_1") (pintype "passive"))
    )
    (net (code "68") (name "Net-(Q7-C)") (class "Default")
      (node (ref "Q7") (pin "2") (pinfunction "C_2") (pintype "passive"))
      (node (ref "R27") (pin "2") (pinfunction "2_2") (pintype "passive"))
    )
    (net (code "69") (name "Net-(Q8-B)") (class "Default")
      (node (ref "Q8") (pin "3") (pinfunction "B_3") (pintype "passive"))
      (node (ref "R8") (pin "1") (pinfunction "1_1") (pintype "passive"))
    )
    (net (code "70") (name "Net-(Q8-C)") (class "Default")
      (node (ref "Q8") (pin "2") (pinfunction "C_2") (pintype "passive"))
      (node (ref "R16") (pin "2") (pinfunction "2_2") (pintype "passive"))
    )
    (net (code "71") (name "Net-(Q9-B)") (class "Default")
      (node (ref "Q9") (pin "3") (pinfunction "B_3") (pintype "passive"))
      (node (ref "R9") (pin "1") (pinfunction "1_1") (pintype "passive"))
    )
    (net (code "72") (name "Net-(Q9-C)") (class "Default")
      (node (ref "Q9") (pin "2") (pinfunction "C_2") (pintype "passive"))
      (node (ref "R18") (pin "2") (pinfunction "2_2") (pintype "passive"))
    )
    (net (code "73") (name "Net-(Q10-B)") (class "Default")
      (node (ref "Q10") (pin "3") (pinfunction "B_3") (pintype "passive"))
      (node (ref "R10") (pin "1") (pinfunction "1_1") (pintype "passive"))
    )
    (net (code "74") (name "Net-(Q10-C)") (class "Default")
      (node (ref "Q10") (pin "2") (pinfunction "C_2") (pintype "passive"))
      (node (ref "R20") (pin "2") (pinfunction "2_2") (pintype "passive"))
    )
    (net (code "75") (name "Net-(Q11-B)") (class "Default")
      (node (ref "Q11") (pin "3") (pinfunction "B_3") (pintype "passive"))
      (node (ref "R11") (pin "1") (pinfunction "1_1") (pintype "passive"))
    )
    (net (code "76") (name "Net-(Q11-C)") (class "Default")
      (node (ref "Q11") (pin "2") (pinfunction "C_2") (pintype "passive"))
      (node (ref "R22") (pin "2") (pinfunction "2_2") (pintype "passive"))
    )
    (net (code "77") (name "Net-(Q12-B)") (class "Default")
      (node (ref "Q12") (pin "3") (pinfunction "B_3") (pintype "passive"))
      (node (ref "R12") (pin "1") (pinfunction "1_1") (pintype "passive"))
    )
    (net (code "78") (name "Net-(Q12-C)") (class "Default")
      (node (ref "Q12") (pin "2") (pinfunction "C_2") (pintype "passive"))
      (node (ref "R24") (pin "2") (pinfunction "2_2") (pintype "passive"))
    )
    (net (code "79") (name "Net-(Q13-B)") (class "Default")
      (node (ref "Q13") (pin "3") (pinfunction "B_3") (pintype "passive"))
      (node (ref "R13") (pin "1") (pinfunction "1_1") (pintype "passive"))
    )
    (net (code "80") (name "Net-(Q13-C)") (class "Default")
      (node (ref "Q13") (pin "2") (pinfunction "C_2") (pintype "passive"))
      (node (ref "R26") (pin "2") (pinfunction "2_2") (pintype "passive"))
    )
    (net (code "81") (name "Net-(Q14-B)") (class "Default")
      (node (ref "Q14") (pin "3") (pinfunction "B_3") (pintype "passive"))
      (node (ref "R14") (pin "1") (pinfunction "1_1") (pintype "passive"))
    )
    (net (code "82") (name "Net-(Q14-C)") (class "Default")
      (node (ref "Q14") (pin "2") (pinfunction "C_2") (pintype "passive"))
      (node (ref "R28") (pin "2") (pinfunction "2_2") (pintype "passive"))
    )
    (net (code "83") (name "VCC") (class "Default")
      (node (ref "C2") (pin "1") (pinfunction "1_1") (pintype "passive"))
      (node (ref "C5") (pin "1") (pinfunction "1_1") (pintype "passive"))
      (node (ref "C7") (pin "1") (pinfunction "1_1") (pintype "passive"))
      (node (ref "D1") (pin "2") (pinfunction "K_2") (pintype "passive"))
      (node (ref "D2") (pin "1") (pinfunction "1_1") (pintype "passive"))
      (node (ref "IC2") (pin "31") (pinfunction "~{EA}/VPP_31") (pintype "passive"))
      (node (ref "IC2") (pin "40") (pinfunction "VCC_40") (pintype "power_in"))
      (node (ref "IC3") (pin "3") (pinfunction "OUT_3") (pintype "passive"))
      (node (ref "IC4") (pin "8") (pinfunction "VCC_8") (pintype "power_in"))
      (node (ref "Q1") (pin "1") (pinfunction "E_1") (pintype "passive"))
      (node (ref "Q10") (pin "1") (pinfunction "E_1") (pintype "passive"))
      (node (ref "Q11") (pin "1") (pinfunction "E_1") (pintype "passive"))
      (node (ref "Q12") (pin "1") (pinfunction "E_1") (pintype "passive"))
      (node (ref "Q13") (pin "1") (pinfunction "E_1") (pintype "passive"))
      (node (ref "Q14") (pin "1") (pinfunction "E_1") (pintype "passive"))
      (node (ref "Q2") (pin "1") (pinfunction "E_1") (pintype "passive"))
      (node (ref "Q3") (pin "1") (pinfunction "E_1") (pintype "passive"))
      (node (ref "Q4") (pin "1") (pinfunction "E_1") (pintype "passive"))
      (node (ref "Q5") (pin "1") (pinfunction "E_1") (pintype "passive"))
      (node (ref "Q6") (pin "1") (pinfunction "E_1") (pintype "passive"))
      (node (ref "Q7") (pin "1") (pinfunction "E_1") (pintype "passive"))
      (node (ref "Q8") (pin "1") (pinfunction "E_1") (pintype "passive"))
      (node (ref "Q9") (pin "1") (pinfunction "E_1") (pintype "passive"))
      (node (ref "R29") (pin "1") (pinfunction "1_1") (pintype "passive"))
      (node (ref "R32") (pin "2") (pinfunction "2_2") (pintype "passive"))
      (node (ref "R33") (pin "2") (pinfunction "2_2") (pintype "passive"))
      (node (ref "R34") (pin "2") (pinfunction "2_2") (pintype "passive"))
      (node (ref "R36") (pin "2") (pinfunction "2_2") (pintype "passive"))
      (node (ref "R37") (pin "2") (pinfunction "2_2") (pintype "passive"))
      (node (ref "SW4") (pin "1") (pinfunction "1_1") (pintype "passive"))
    )
    (net (code "84") (name "VDD") (class "Default")
      (node (ref "IC1") (pin "14") (pinfunction "VDD_14") (pintype "power_in"))
    )
    (net (code "85") (name "unconnected-(IC2-ALE{slash}~{PROG}-Pad30)") (class "Default")
      (node (ref "IC2") (pin "30") (pinfunction "ALE/~{PROG}_30") (pintype "passive"))
    )
    (net (code "86") (name "unconnected-(IC2-P1.6-Pad7)") (class "Default")
      (node (ref "IC2") (pin "7") (pinfunction "P1.6_7") (pintype "passive"))
    )
    (net (code "87") (name "unconnected-(IC2-P1.7-Pad8)") (class "Default")
      (node (ref "IC2") (pin "8") (pinfunction "P1.7_8") (pintype "passive"))
    )
    (net (code "88") (name "unconnected-(IC2-~{PSEN}-Pad29)") (class "Default")
      (node (ref "IC2") (pin "29") (pinfunction "~{PSEN}_29") (pintype "passive"))
    )
    (net (code "89") (name "unconnected-(IC2-~{RD}{slash}P3.7-Pad17)") (class "Default")
      (node (ref "IC2") (pin "17") (pinfunction "~{RD}/P3.7_17") (pintype "passive"))
    )
    (net (code "90") (name "unconnected-(IC2-~{WR}{slash}P3.6-Pad16)") (class "Default")
      (node (ref "IC2") (pin "16") (pinfunction "~{WR}/P3.6_16") (pintype "passive"))
    )
    (net (code "91") (name "unconnected-(IC4-SQW{slash}OUT-Pad7)") (class "Default")
      (node (ref "IC4") (pin "7") (pinfunction "SQW/OUT_7") (pintype "bidirectional"))
    )
    (net (code "92") (name "unconnected-(JDC1-S-Pad3)") (class "Default")
      (node (ref "JDC1") (pin "3") (pinfunction "S_3") (pintype "power_in"))
    )
    (net (code "93") (name "unconnected-(R35-Pad2)") (class "Default")
      (node (ref "R35") (pin "2") (pinfunction "2_2") (pintype "passive"))
    )
  )
)
